# 1_MICROCONTROLADOR.net
KiCad netlist of a schematic drawn in Altium Designer
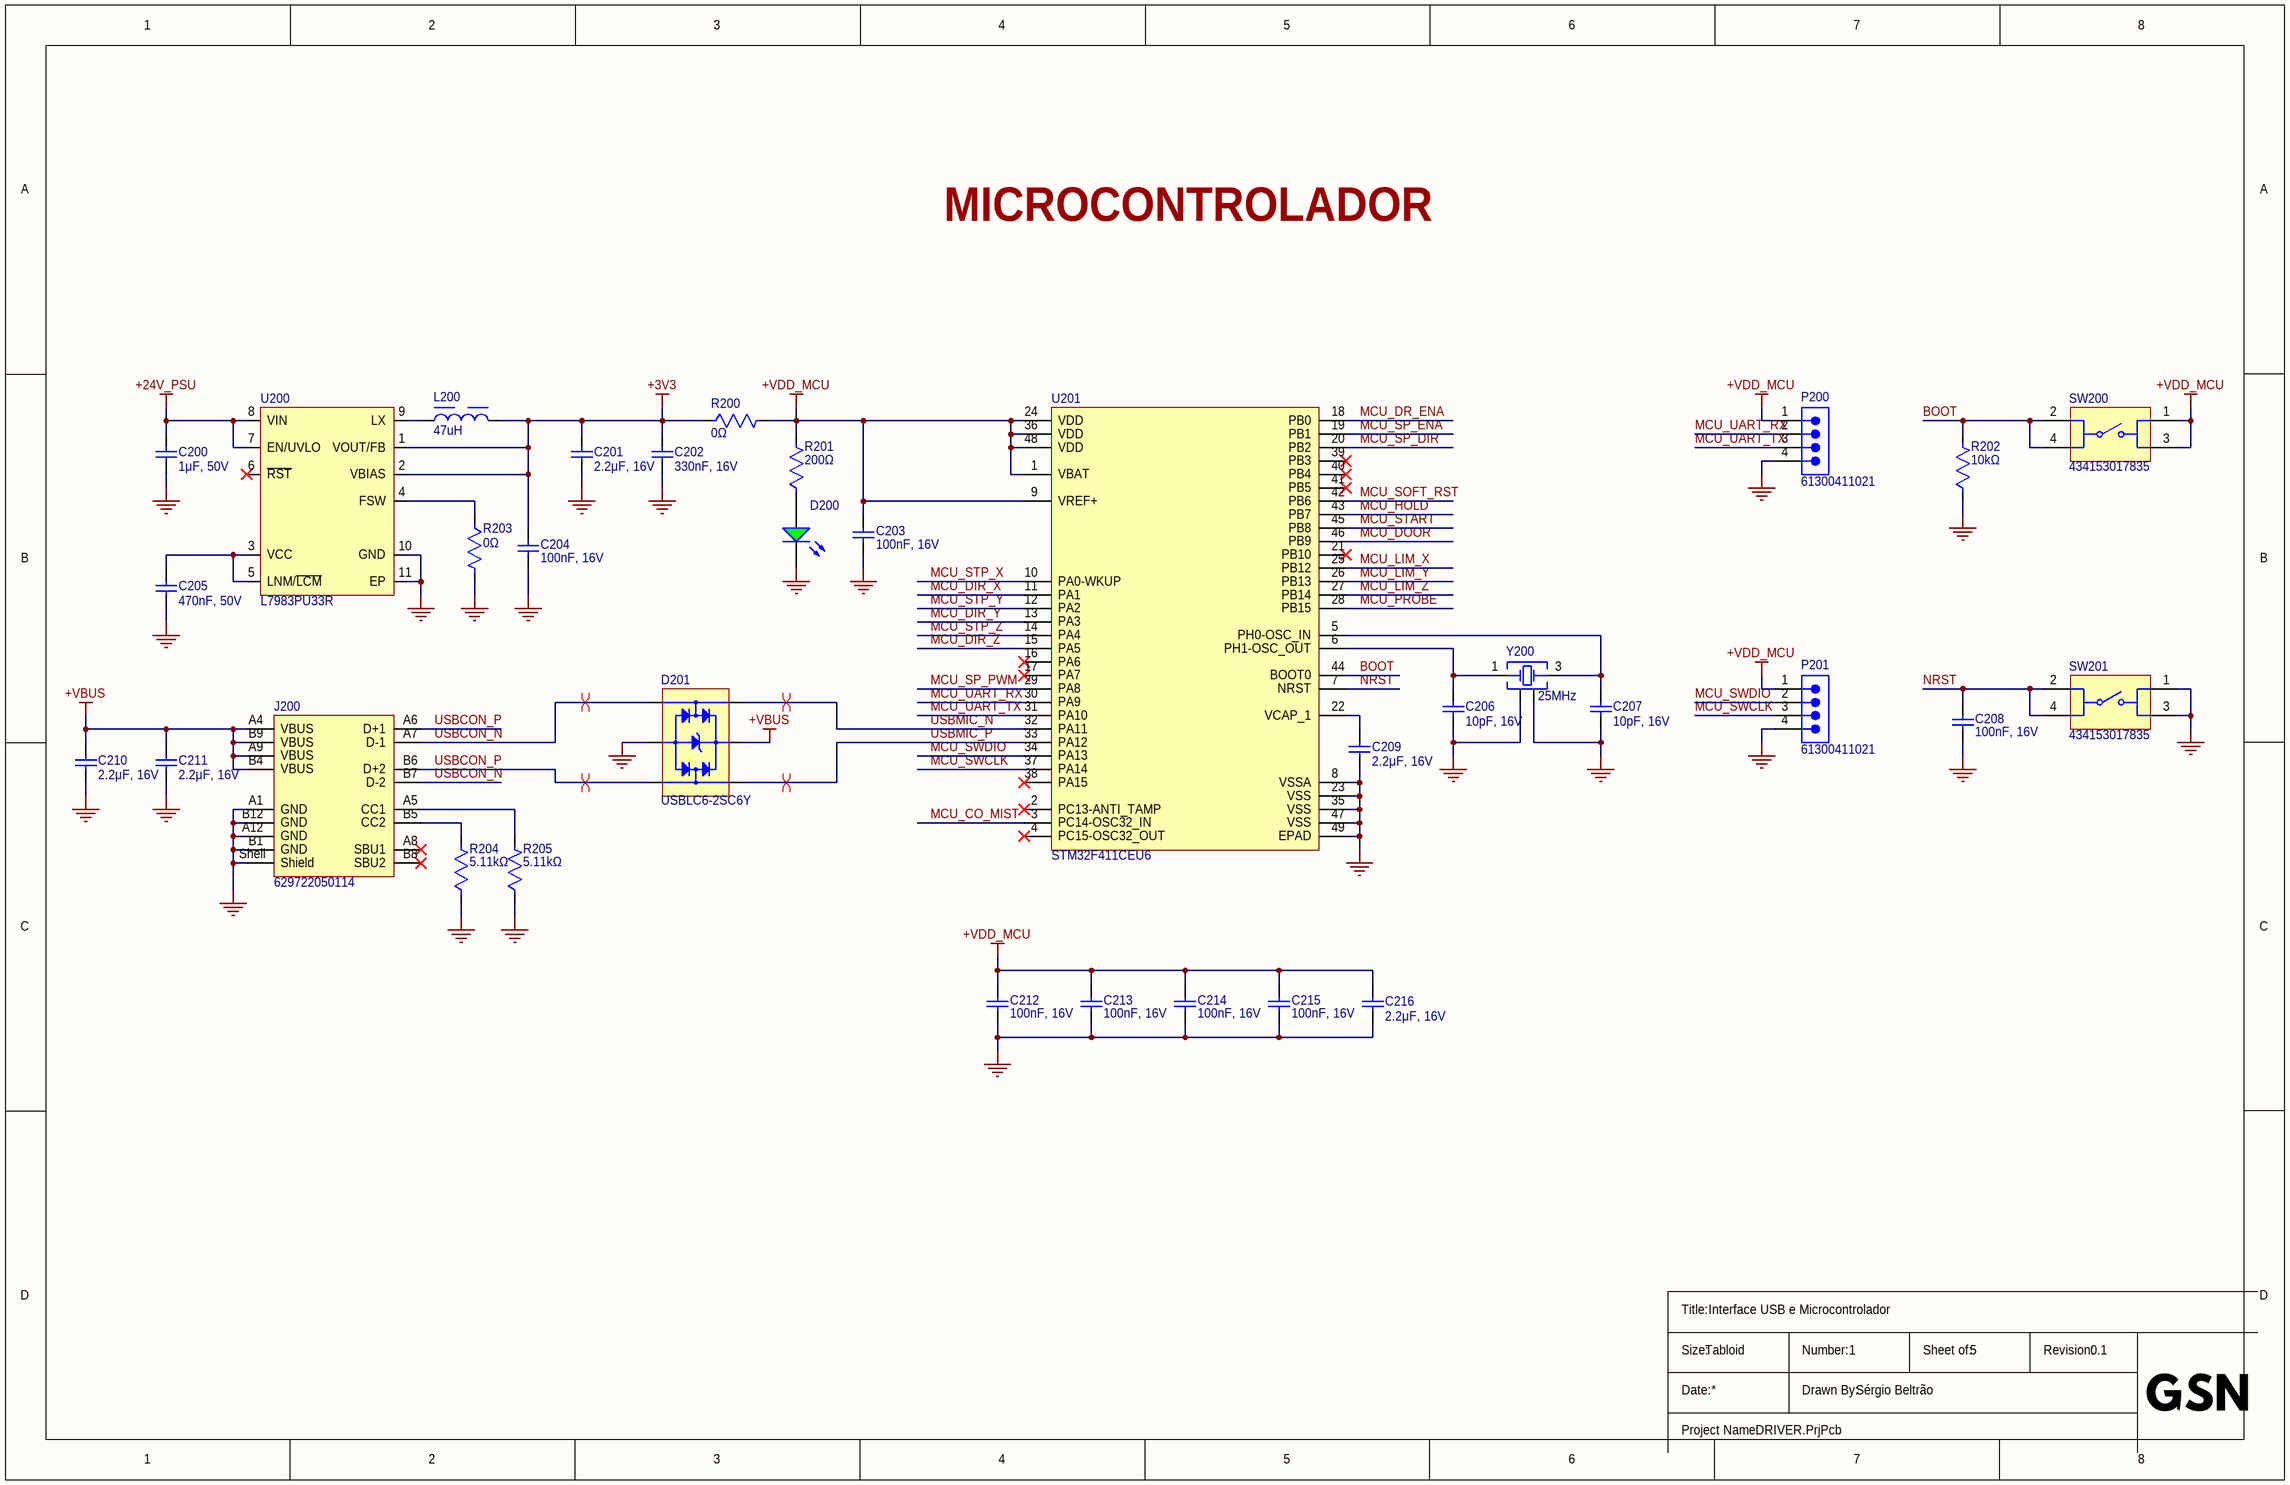
[diagram p0: 1_MICROCONTROLADOR.SchDoc]

(export (version "E")
  (design (tool "Eeschema 10.0.6"))
  (components
    (comp (ref "C200")
      (value "1μF, 50V")
      (footprint "WCAP-CSGP_0805_L2W1.25H1.25")
      (description "WCAP-CSGP Multilayer Ceramic Chip Capacitor, General Purpose, size 0805, 1μF, 50V")
      (fields
        (field (name "MANUFACTURER PART NUMBER") "885012207103R")
        (field (name "MANUFACTURER") "Wurth Elektronik")
      )
      (libsource (lib "WE - Passive Components") (part "Capacitor_Non-Polarized"))
    )
    (comp (ref "C201")
      (value "2.2μF, 16V")
      (footprint "WCAP-CSGP_0603_L1.6W0.8H0.8_Wave")
      (description "WCAP-CSGP Multilayer Ceramic Chip Capacitor, General Purpose, size 0603, 2.2μF, 16V")
      (fields
        (field (name "MANUFACTURER PART NUMBER") "885012106029")
        (field (name "MANUFACTURER") "Wurth Elektronik")
      )
      (libsource (lib "WE - Passive Components") (part "Capacitor_Non-Polarized"))
    )
    (comp (ref "C202")
      (value "330nF, 16V")
      (footprint "WCAP-CSGP_0603_L1.6W0.8H0.8_Wave")
      (description "WCAP-CSGP Multilayer Ceramic Chip Capacitor, General Purpose, size 0603, 330nF, 16V")
      (fields
        (field (name "MANUFACTURER PART NUMBER") "885012206049")
        (field (name "MANUFACTURER") "Wurth Elektronik")
      )
      (libsource (lib "WE - Passive Components") (part "Capacitor_Non-Polarized"))
    )
    (comp (ref "C203")
      (value "100nF, 16V")
      (footprint "WCAP-CSGP_0603_L1.6W0.8H0.8_Wave")
      (description "WCAP-CSGP Multilayer Ceramic Chip Capacitor, General Purpose, size 0603, 100nF, 16V")
      (fields
        (field (name "MANUFACTURER PART NUMBER") "885012206046")
        (field (name "MANUFACTURER") "Wurth Elektronik")
      )
      (libsource (lib "WE - Passive Components") (part "Capacitor_Non-Polarized"))
    )
    (comp (ref "C204")
      (value "100nF, 16V")
      (footprint "WCAP-CSGP_0603_L1.6W0.8H0.8_Wave")
      (description "WCAP-CSGP Multilayer Ceramic Chip Capacitor, General Purpose, size 0603, 100nF, 16V")
      (fields
        (field (name "MANUFACTURER PART NUMBER") "885012206046")
        (field (name "MANUFACTURER") "Wurth Elektronik")
      )
      (libsource (lib "WE - Passive Components") (part "Capacitor_Non-Polarized"))
    )
    (comp (ref "C205")
      (value "470nF, 50V")
      (footprint "WCAP-CSGP_0805_L2W1.25H1.25")
      (description "WCAP-CSGP Multilayer Ceramic Chip Capacitor, General Purpose, size 0805, 470nF, 50V")
      (fields
        (field (name "MANUFACTURER PART NUMBER") "885012207102")
        (field (name "MANUFACTURER") "Wurth Elektronik")
      )
      (libsource (lib "WE - Passive Components") (part "Capacitor_Non-Polarized"))
    )
    (comp (ref "C206")
      (value "10pF, 16V")
      (footprint "WCAP-CSGP_0603_L1.6W0.8H0.8_Wave")
      (description "WCAP-CSGP Multilayer Ceramic Chip Capacitor, General Purpose, size 0603, 10pF, 16V")
      (fields
        (field (name "MANUFACTURER PART NUMBER") "885012006017")
        (field (name "MANUFACTURER") "Wurth Elektronik")
      )
      (libsource (lib "WE - Passive Components") (part "Capacitor_Non-Polarized"))
    )
    (comp (ref "C207")
      (value "10pF, 16V")
      (footprint "WCAP-CSGP_0603_L1.6W0.8H0.8_Wave")
      (description "WCAP-CSGP Multilayer Ceramic Chip Capacitor, General Purpose, size 0603, 10pF, 16V")
      (fields
        (field (name "MANUFACTURER PART NUMBER") "885012006017")
        (field (name "MANUFACTURER") "Wurth Elektronik")
      )
      (libsource (lib "WE - Passive Components") (part "Capacitor_Non-Polarized"))
    )
    (comp (ref "C208")
      (value "100nF, 16V")
      (footprint "WCAP-CSGP_0603_L1.6W0.8H0.8_Wave")
      (description "WCAP-CSGP Multilayer Ceramic Chip Capacitor, General Purpose, size 0603, 100nF, 16V")
      (fields
        (field (name "MANUFACTURER PART NUMBER") "885012206046")
        (field (name "MANUFACTURER") "Wurth Elektronik")
      )
      (libsource (lib "WE - Passive Components") (part "Capacitor_Non-Polarized"))
    )
    (comp (ref "C209")
      (value "2.2μF, 16V")
      (footprint "WCAP-CSGP_0603_L1.6W0.8H0.8_Wave")
      (description "WCAP-CSGP Multilayer Ceramic Chip Capacitor, General Purpose, size 0603, 2.2μF, 16V")
      (fields
        (field (name "MANUFACTURER PART NUMBER") "885012106029")
        (field (name "MANUFACTURER") "Wurth Elektronik")
      )
      (libsource (lib "WE - Passive Components") (part "Capacitor_Non-Polarized"))
    )
    (comp (ref "C210")
      (value "2.2μF, 16V")
      (footprint "WCAP-CSGP_0603_L1.6W0.8H0.8_Wave")
      (description "WCAP-CSGP Multilayer Ceramic Chip Capacitor, General Purpose, size 0603, 2.2μF, 16V")
      (fields
        (field (name "MANUFACTURER PART NUMBER") "885012106029")
        (field (name "MANUFACTURER") "Wurth Elektronik")
      )
      (libsource (lib "WE - Passive Components") (part "Capacitor_Non-Polarized"))
    )
    (comp (ref "C211")
      (value "2.2μF, 16V")
      (footprint "WCAP-CSGP_0603_L1.6W0.8H0.8_Wave")
      (description "WCAP-CSGP Multilayer Ceramic Chip Capacitor, General Purpose, size 0603, 2.2μF, 16V")
      (fields
        (field (name "MANUFACTURER PART NUMBER") "885012106029")
        (field (name "MANUFACTURER") "Wurth Elektronik")
      )
      (libsource (lib "WE - Passive Components") (part "Capacitor_Non-Polarized"))
    )
    (comp (ref "C212")
      (value "100nF, 16V")
      (footprint "WCAP-CSGP_0603_L1.6W0.8H0.8_Wave")
      (description "WCAP-CSGP Multilayer Ceramic Chip Capacitor, General Purpose, size 0603, 100nF, 16V")
      (fields
        (field (name "MANUFACTURER PART NUMBER") "885012206046")
        (field (name "MANUFACTURER") "Wurth Elektronik")
      )
      (libsource (lib "WE - Passive Components") (part "Capacitor_Non-Polarized"))
    )
    (comp (ref "C213")
      (value "100nF, 16V")
      (footprint "WCAP-CSGP_0603_L1.6W0.8H0.8_Wave")
      (description "WCAP-CSGP Multilayer Ceramic Chip Capacitor, General Purpose, size 0603, 100nF, 16V")
      (fields
        (field (name "MANUFACTURER PART NUMBER") "885012206046")
        (field (name "MANUFACTURER") "Wurth Elektronik")
      )
      (libsource (lib "WE - Passive Components") (part "Capacitor_Non-Polarized"))
    )
    (comp (ref "C214")
      (value "100nF, 16V")
      (footprint "WCAP-CSGP_0603_L1.6W0.8H0.8_Wave")
      (description "WCAP-CSGP Multilayer Ceramic Chip Capacitor, General Purpose, size 0603, 100nF, 16V")
      (fields
        (field (name "MANUFACTURER PART NUMBER") "885012206046")
        (field (name "MANUFACTURER") "Wurth Elektronik")
      )
      (libsource (lib "WE - Passive Components") (part "Capacitor_Non-Polarized"))
    )
    (comp (ref "C215")
      (value "100nF, 16V")
      (footprint "WCAP-CSGP_0603_L1.6W0.8H0.8_Wave")
      (description "WCAP-CSGP Multilayer Ceramic Chip Capacitor, General Purpose, size 0603, 100nF, 16V")
      (fields
        (field (name "MANUFACTURER PART NUMBER") "885012206046")
        (field (name "MANUFACTURER") "Wurth Elektronik")
      )
      (libsource (lib "WE - Passive Components") (part "Capacitor_Non-Polarized"))
    )
    (comp (ref "C216")
      (value "2.2μF, 16V")
      (footprint "WCAP-CSGP_0603_L1.6W0.8H0.8_Wave")
      (description "WCAP-CSGP Multilayer Ceramic Chip Capacitor, General Purpose, size 0603, 2.2μF, 16V")
      (fields
        (field (name "MANUFACTURER PART NUMBER") "885012106029")
        (field (name "MANUFACTURER") "Wurth Elektronik")
      )
      (libsource (lib "WE - Passive Components") (part "Capacitor_Non-Polarized"))
    )
    (comp (ref "D200")
      (value "Bright Green, 2V, 140deg")
      (footprint "WL-SMCW_0603_150060xx75000")
      (description "WL-SMCW Mono-color Chip LED Waterclear, SMT, size 0603, Bright Green, 2V, 140°")
      (fields
        (field (name "MANUFACTURER PART NUMBER") "150060VS75000")
        (field (name "MANUFACTURER") "Wurth Elektronik")
      )
      (libsource (lib "WE - Optoelectronic Components") (part "LED_Green_2A-1K"))
    )
    (comp (ref "D201")
      (value "USBLC6-2SC6Y")
      (footprint "SOT-23-6")
      (description "TVS DIODE 5.25VWM 17VC SOT23-6")
      (fields (field (name "MANUFACTURER") "STMicroelectronics"))
      (libsource (lib "TVS-Diodes") (part "USBLC6-2SC6Y"))
    )
    (comp (ref "J200")
      (value "629722050114")
      (footprint "629722050114")
      (description "WR-COM USB 2.0 Vertical SMT")
      (fields (field (name "MANUFACTURER") "Wurth Elektronik"))
      (libsource (lib "WE - Electromechanical Components") (part "USB 2.0_Type C_Receptacle_1 Port"))
    )
    (comp (ref "L200")
      (value "47uH")
      (footprint "WE-MAIA_3015")
      (description "WE-MAIA SMT Power Inductor, size 3015, 47uH, 0.5A, 2300mohm")
      (fields
        (field (name "MANUFACTURER PART NUMBER") "78438335470")
        (field (name "MANUFACTURER") "Wurth Elektronik")
      )
      (libsource (lib "WE - Passive Components") (part "Inductor - 3"))
    )
    (comp (ref "P200")
      (value "61300411021")
      (footprint "61300411021")
      (description "WR-PHD Pin Header, THT, Angled, pitch 2.54mm, 1 Row, 4P")
      (fields (field (name "MANUFACTURER") "Wurth Elektronik"))
      (libsource (lib "WE - Electromechanical Components") (part "Header_Male_1R_04P"))
    )
    (comp (ref "P201")
      (value "61300411021")
      (footprint "61300411021")
      (description "WR-PHD Pin Header, THT, Angled, pitch 2.54mm, 1 Row, 4P")
      (fields (field (name "MANUFACTURER") "Wurth Elektronik"))
      (libsource (lib "WE - Electromechanical Components") (part "Header_Male_1R_04P"))
    )
    (comp (ref "R200")
      (value "0Ω")
      (footprint "0805-WAVE")
      (description "RES 0 OHM 1% 1/8W 0805")
      (fields
        (field (name "MANUFACTURER") "Yageo Group")
        (field (name "MANUFACTURER PART NUMBER") "RC0805FR-070RL")
      )
      (libsource (lib "Resistors-0805-E96-Yageo") (part "RC0805FR-070RL"))
    )
    (comp (ref "R201")
      (value "200Ω")
      (footprint "0603-WAVE")
      (description "RES 200 OHM 1% 1/10W 0603")
      (fields
        (field (name "MANUFACTURER PART NUMBER") "RC0603FR-07200RL")
        (field (name "MANUFACTURER") "Yageo Group")
      )
      (libsource (lib "Resistors-0603-E96-Yageo") (part "RC0603FR-07200RL"))
    )
    (comp (ref "R202")
      (value "10kΩ")
      (footprint "0603-WAVE")
      (description "RES 10K OHM 1% 1/10W 0603")
      (fields
        (field (name "MANUFACTURER PART NUMBER") "RC0603FR-0710KL")
        (field (name "MANUFACTURER") "Yageo Group")
      )
      (libsource (lib "Resistors-0603-E96-Yageo") (part "RC0603FR-0710KL"))
    )
    (comp (ref "R203")
      (value "0Ω")
      (footprint "0603-WAVE")
      (description "RES 0 OHM 1% 1/10W 0603")
      (fields
        (field (name "MANUFACTURER PART NUMBER") "RC0603FR-070RL")
        (field (name "MANUFACTURER") "Yageo Group")
      )
      (libsource (lib "Resistors-0603-E96-Yageo") (part "RC0603FR-070RL"))
    )
    (comp (ref "R204")
      (value "5.11kΩ")
      (footprint "0603-WAVE")
      (description "RES 5.11K OHM 1% 1/10W 0603")
      (fields
        (field (name "MANUFACTURER PART NUMBER") "RC0603FR-075K11L")
        (field (name "MANUFACTURER") "Yageo Group")
      )
      (libsource (lib "Resistors-0603-E96-Yageo") (part "RC0603FR-075K11L"))
    )
    (comp (ref "R205")
      (value "5.11kΩ")
      (footprint "0603-WAVE")
      (description "RES 5.11K OHM 1% 1/10W 0603")
      (fields
        (field (name "MANUFACTURER PART NUMBER") "RC0603FR-075K11L")
        (field (name "MANUFACTURER") "Yageo Group")
      )
      (libsource (lib "Resistors-0603-E96-Yageo") (part "RC0603FR-075K11L"))
    )
    (comp (ref "SW200")
      (value "434153017835")
      (footprint "434153017835")
      (description "WS-TASV J-Bend SMT Tact Switch, 3.5mm x 2.9mm x 1.7mm, SPST-NO, 350gf, 12V, 50mA")
      (fields (field (name "MANUFACTURER") "Wurth Elektronik"))
      (libsource (lib "WE - Electromechanical Components") (part "SPST-NO_4P_24-13"))
    )
    (comp (ref "SW201")
      (value "434153017835")
      (footprint "434153017835")
      (description "WS-TASV J-Bend SMT Tact Switch, 3.5mm x 2.9mm x 1.7mm, SPST-NO, 350gf, 12V, 50mA")
      (fields (field (name "MANUFACTURER") "Wurth Elektronik"))
      (libsource (lib "WE - Electromechanical Components") (part "SPST-NO_4P_24-13"))
    )
    (comp (ref "U200")
      (value "L7983PU33R")
      (footprint "10-WFDFN-EP")
      (description "IC REG BUCK 3.3V 300MA 10DFN")
      (fields (field (name "MANUFACTURER") "STMicroelectronics"))
      (libsource (lib "Voltage-Regulators") (part "L7983PU33R"))
    )
    (comp (ref "U201")
      (value "STM32F411CEU6")
      (footprint "UFQFN-48-7X7_EXPOSED_PAD")
      (description "IC MCU 32BIT 512KB FLSH 48UFQFPN")
      (fields (field (name "MANUFACTURER") "STMicroelectronics"))
      (libsource (lib "Microcontrollers") (part "STM32F411CEU6"))
    )
    (comp (ref "Y200")
      (value "25MHz")
      (footprint "WE-XTAL_IQXC-42")
      (description "WE-XTAL Quartz Crystal, IQXC-42, 25MHz, +/-15ppm")
      (fields
        (field (name "MANUFACTURER PART NUMBER") "830069494")
        (field (name "MANUFACTURER") "Wurth Elektronik")
      )
      (libsource (lib "WE - Passive Components") (part "WE-XTAL_IQXC-42"))
    )
  )
  (nets
    (net (code "1") (name "+3V3") (class "Default")
      (node (ref "C201") (pin "2") (pinfunction "2_2") (pintype "passive"))
      (node (ref "C202") (pin "2") (pinfunction "2_2") (pintype "passive"))
      (node (ref "C204") (pin "2") (pinfunction "2_2") (pintype "passive"))
      (node (ref "L200") (pin "2") (pinfunction "2_2") (pintype "passive"))
      (node (ref "R200") (pin "1") (pinfunction "1_1") (pintype "passive"))
      (node (ref "U200") (pin "1") (pinfunction "VOUT/FB_1") (pintype "passive"))
      (node (ref "U200") (pin "2") (pinfunction "VBIAS_2") (pintype "passive"))
    )
    (net (code "2") (name "+24V_PSU") (class "Default")
      (node (ref "C200") (pin "2") (pinfunction "2_2") (pintype "passive"))
      (node (ref "U200") (pin "7") (pinfunction "EN/UVLO_7") (pintype "passive"))
      (node (ref "U200") (pin "8") (pinfunction "VIN_8") (pintype "passive"))
    )
    (net (code "3") (name "+VBUS") (class "Default")
      (node (ref "C210") (pin "2") (pinfunction "2_2") (pintype "passive"))
      (node (ref "C211") (pin "2") (pinfunction "2_2") (pintype "passive"))
      (node (ref "D201") (pin "5") (pinfunction "VBUS_5") (pintype "passive"))
      (node (ref "J200") (pin "A4") (pinfunction "VBUS_A4") (pintype "passive"))
      (node (ref "J200") (pin "A9") (pinfunction "VBUS_A9") (pintype "passive"))
      (node (ref "J200") (pin "B4") (pinfunction "VBUS_B4") (pintype "passive"))
      (node (ref "J200") (pin "B9") (pinfunction "VBUS_B9") (pintype "passive"))
    )
    (net (code "4") (name "+VDD_MCU") (class "Default")
      (node (ref "C203") (pin "2") (pinfunction "2_2") (pintype "passive"))
      (node (ref "C212") (pin "2") (pinfunction "2_2") (pintype "passive"))
      (node (ref "C213") (pin "2") (pinfunction "2_2") (pintype "passive"))
      (node (ref "C214") (pin "2") (pinfunction "2_2") (pintype "passive"))
      (node (ref "C215") (pin "2") (pinfunction "2_2") (pintype "passive"))
      (node (ref "C216") (pin "2") (pinfunction "2_2") (pintype "passive"))
      (node (ref "P200") (pin "1") (pinfunction "1_1") (pintype "passive"))
      (node (ref "P201") (pin "1") (pinfunction "1_1") (pintype "passive"))
      (node (ref "R200") (pin "2") (pinfunction "2_2") (pintype "passive"))
      (node (ref "R201") (pin "2") (pinfunction "2_2") (pintype "passive"))
      (node (ref "SW200") (pin "1") (pinfunction "1_1") (pintype "passive"))
      (node (ref "SW200") (pin "3") (pinfunction "3_3") (pintype "passive"))
      (node (ref "U201") (pin "1") (pinfunction "VBAT_1") (pintype "passive"))
      (node (ref "U201") (pin "24") (pinfunction "VDD_24") (pintype "passive"))
      (node (ref "U201") (pin "36") (pinfunction "VDD_36") (pintype "passive"))
      (node (ref "U201") (pin "48") (pinfunction "VDD_48") (pintype "passive"))
      (node (ref "U201") (pin "9") (pinfunction "VREF+_9") (pintype "passive"))
    )
    (net (code "5") (name "/BOOT") (class "Default")
      (node (ref "R202") (pin "2") (pinfunction "2_2") (pintype "passive"))
      (node (ref "SW200") (pin "2") (pinfunction "2_2") (pintype "passive"))
      (node (ref "SW200") (pin "4") (pinfunction "4_4") (pintype "passive"))
      (node (ref "U201") (pin "44") (pinfunction "BOOT0_44") (pintype "passive"))
    )
    (net (code "6") (name "/MCU_CO_MIST") (class "Default")
      (node (ref "U201") (pin "3") (pinfunction "PC14-OSC32_IN_3") (pintype "passive"))
    )
    (net (code "7") (name "/MCU_DIR_X") (class "Default")
      (node (ref "U201") (pin "11") (pinfunction "PA1_11") (pintype "passive"))
    )
    (net (code "8") (name "/MCU_DIR_Y") (class "Default")
      (node (ref "U201") (pin "13") (pinfunction "PA3_13") (pintype "passive"))
    )
    (net (code "9") (name "/MCU_DIR_Z") (class "Default")
      (node (ref "U201") (pin "15") (pinfunction "PA5_15") (pintype "passive"))
    )
    (net (code "10") (name "/MCU_DOOR") (class "Default")
      (node (ref "U201") (pin "46") (pinfunction "PB9_46") (pintype "passive"))
    )
    (net (code "11") (name "/MCU_DR_ENA") (class "Default")
      (node (ref "U201") (pin "18") (pinfunction "PB0_18") (pintype "passive"))
    )
    (net (code "12") (name "/MCU_HOLD") (class "Default")
      (node (ref "U201") (pin "43") (pinfunction "PB7_43") (pintype "passive"))
    )
    (net (code "13") (name "/MCU_LIM_X") (class "Default")
      (node (ref "U201") (pin "25") (pinfunction "PB12_25") (pintype "passive"))
    )
    (net (code "14") (name "/MCU_LIM_Y") (class "Default")
      (node (ref "U201") (pin "26") (pinfunction "PB13_26") (pintype "passive"))
    )
    (net (code "15") (name "/MCU_LIM_Z") (class "Default")
      (node (ref "U201") (pin "27") (pinfunction "PB14_27") (pintype "passive"))
    )
    (net (code "16") (name "/MCU_PROBE") (class "Default")
      (node (ref "U201") (pin "28") (pinfunction "PB15_28") (pintype "passive"))
    )
    (net (code "17") (name "/MCU_SOFT_RST") (class "Default")
      (node (ref "U201") (pin "42") (pinfunction "PB6_42") (pintype "passive"))
    )
    (net (code "18") (name "/MCU_SP_DIR") (class "Default")
      (node (ref "U201") (pin "20") (pinfunction "PB2_20") (pintype "passive"))
    )
    (net (code "19") (name "/MCU_SP_ENA") (class "Default")
      (node (ref "U201") (pin "19") (pinfunction "PB1_19") (pintype "passive"))
    )
    (net (code "20") (name "/MCU_SP_PWM") (class "Default")
      (node (ref "U201") (pin "29") (pinfunction "PA8_29") (pintype "passive"))
    )
    (net (code "21") (name "/MCU_START") (class "Default")
      (node (ref "U201") (pin "45") (pinfunction "PB8_45") (pintype "passive"))
    )
    (net (code "22") (name "/MCU_STP_X") (class "Default")
      (node (ref "U201") (pin "10") (pinfunction "PA0-WKUP_10") (pintype "passive"))
    )
    (net (code "23") (name "/MCU_STP_Y") (class "Default")
      (node (ref "U201") (pin "12") (pinfunction "PA2_12") (pintype "passive"))
    )
    (net (code "24") (name "/MCU_STP_Z") (class "Default")
      (node (ref "U201") (pin "14") (pinfunction "PA4_14") (pintype "passive"))
    )
    (net (code "25") (name "/MCU_SWCLK") (class "Default")
      (node (ref "P201") (pin "3") (pinfunction "3_3") (pintype "passive"))
      (node (ref "U201") (pin "37") (pinfunction "PA14_37") (pintype "passive"))
    )
    (net (code "26") (name "/MCU_SWDIO") (class "Default")
      (node (ref "P201") (pin "2") (pinfunction "2_2") (pintype "passive"))
      (node (ref "U201") (pin "34") (pinfunction "PA13_34") (pintype "passive"))
    )
    (net (code "27") (name "/MCU_UART_RX") (class "Default")
      (node (ref "P200") (pin "2") (pinfunction "2_2") (pintype "passive"))
      (node (ref "U201") (pin "30") (pinfunction "PA9_30") (pintype "passive"))
    )
    (net (code "28") (name "/MCU_UART_TX") (class "Default")
      (node (ref "P200") (pin "3") (pinfunction "3_3") (pintype "passive"))
      (node (ref "U201") (pin "31") (pinfunction "PA10_31") (pintype "passive"))
    )
    (net (code "29") (name "/NRST") (class "Default")
      (node (ref "C208") (pin "2") (pinfunction "2_2") (pintype "passive"))
      (node (ref "SW201") (pin "2") (pinfunction "2_2") (pintype "passive"))
      (node (ref "SW201") (pin "4") (pinfunction "4_4") (pintype "passive"))
      (node (ref "U201") (pin "7") (pinfunction "NRST_7") (pintype "passive"))
    )
    (net (code "30") (name "/USBCON_N") (class "Default")
      (node (ref "D201") (pin "1") (pinfunction "IO1_1") (pintype "passive"))
      (node (ref "J200") (pin "A7") (pinfunction "D-1_A7") (pintype "passive"))
      (node (ref "J200") (pin "B7") (pinfunction "D-2_B7") (pintype "passive"))
    )
    (net (code "31") (name "/USBCON_P") (class "Default")
      (node (ref "D201") (pin "3") (pinfunction "IO2_3") (pintype "passive"))
      (node (ref "J200") (pin "A6") (pinfunction "D+1_A6") (pintype "passive"))
      (node (ref "J200") (pin "B6") (pinfunction "D+2_B6") (pintype "passive"))
    )
    (net (code "32") (name "/USBMIC_N") (class "Default")
      (node (ref "D201") (pin "6") (pinfunction "IO1_6") (pintype "passive"))
      (node (ref "U201") (pin "32") (pinfunction "PA11_32") (pintype "passive"))
    )
    (net (code "33") (name "/USBMIC_P") (class "Default")
      (node (ref "D201") (pin "4") (pinfunction "IO2_4") (pintype "passive"))
      (node (ref "U201") (pin "33") (pinfunction "PA12_33") (pintype "passive"))
    )
    (net (code "34") (name "GND") (class "Default")
      (node (ref "C200") (pin "1") (pinfunction "1_1") (pintype "passive"))
      (node (ref "C201") (pin "1") (pinfunction "1_1") (pintype "passive"))
      (node (ref "C202") (pin "1") (pinfunction "1_1") (pintype "passive"))
      (node (ref "C203") (pin "1") (pinfunction "1_1") (pintype "passive"))
      (node (ref "C204") (pin "1") (pinfunction "1_1") (pintype "passive"))
      (node (ref "C205") (pin "1") (pinfunction "1_1") (pintype "passive"))
      (node (ref "C206") (pin "1") (pinfunction "1_1") (pintype "passive"))
      (node (ref "C207") (pin "1") (pinfunction "1_1") (pintype "passive"))
      (node (ref "C208") (pin "1") (pinfunction "1_1") (pintype "passive"))
      (node (ref "C209") (pin "1") (pinfunction "1_1") (pintype "passive"))
      (node (ref "C210") (pin "1") (pinfunction "1_1") (pintype "passive"))
      (node (ref "C211") (pin "1") (pinfunction "1_1") (pintype "passive"))
      (node (ref "C212") (pin "1") (pinfunction "1_1") (pintype "passive"))
      (node (ref "C213") (pin "1") (pinfunction "1_1") (pintype "passive"))
      (node (ref "C214") (pin "1") (pinfunction "1_1") (pintype "passive"))
      (node (ref "C215") (pin "1") (pinfunction "1_1") (pintype "passive"))
      (node (ref "C216") (pin "1") (pinfunction "1_1") (pintype "passive"))
      (node (ref "D200") (pin "1") (pinfunction "K_1") (pintype "passive"))
      (node (ref "D201") (pin "2") (pinfunction "GND_2") (pintype "passive"))
      (node (ref "J200") (pin "A1") (pinfunction "GND_A1") (pintype "passive"))
      (node (ref "J200") (pin "A12") (pinfunction "GND_A12") (pintype "passive"))
      (node (ref "J200") (pin "B1") (pinfunction "GND_B1") (pintype "passive"))
      (node (ref "J200") (pin "B12") (pinfunction "GND_B12") (pintype "passive"))
      (node (ref "J200") (pin "Shell") (pinfunction "Shield_Shell") (pintype "passive"))
      (node (ref "P200") (pin "4") (pinfunction "4_4") (pintype "passive"))
      (node (ref "P201") (pin "4") (pinfunction "4_4") (pintype "passive"))
      (node (ref "R202") (pin "1") (pinfunction "1_1") (pintype "passive"))
      (node (ref "R203") (pin "2") (pinfunction "2_2") (pintype "passive"))
      (node (ref "R204") (pin "1") (pinfunction "1_1") (pintype "passive"))
      (node (ref "R205") (pin "1") (pinfunction "1_1") (pintype "passive"))
      (node (ref "SW201") (pin "1") (pinfunction "1_1") (pintype "passive"))
      (node (ref "SW201") (pin "3") (pinfunction "3_3") (pintype "passive"))
      (node (ref "U200") (pin "10") (pinfunction "GND_10") (pintype "passive"))
      (node (ref "U200") (pin "11") (pinfunction "EP_11") (pintype "passive"))
      (node (ref "U201") (pin "23") (pinfunction "VSS_23") (pintype "passive"))
      (node (ref "U201") (pin "35") (pinfunction "VSS_35") (pintype "passive"))
      (node (ref "U201") (pin "47") (pinfunction "VSS_47") (pintype "passive"))
      (node (ref "U201") (pin "49") (pinfunction "EPAD_49") (pintype "passive"))
      (node (ref "U201") (pin "8") (pinfunction "VSSA_8") (pintype "passive"))
      (node (ref "Y200") (pin "2") (pinfunction "GND_&_Lid_2") (pintype "passive"))
      (node (ref "Y200") (pin "4") (pinfunction "GND_&_Lid_4") (pintype "passive"))
    )
    (net (code "35") (name "Net-(D200-A)") (class "Default")
      (node (ref "D200") (pin "2") (pinfunction "A_2") (pintype "passive"))
      (node (ref "R201") (pin "1") (pinfunction "1_1") (pintype "passive"))
    )
    (net (code "36") (name "Net-(J200-CC1)") (class "Default")
      (node (ref "J200") (pin "A5") (pinfunction "CC1_A5") (pintype "passive"))
      (node (ref "R205") (pin "2") (pinfunction "2_2") (pintype "passive"))
    )
    (net (code "37") (name "Net-(J200-CC2)") (class "Default")
      (node (ref "J200") (pin "B5") (pinfunction "CC2_B5") (pintype "passive"))
      (node (ref "R204") (pin "2") (pinfunction "2_2") (pintype "passive"))
    )
    (net (code "38") (name "Net-(U200-FSW)") (class "Default")
      (node (ref "R203") (pin "1") (pinfunction "1_1") (pintype "passive"))
      (node (ref "U200") (pin "4") (pinfunction "FSW_4") (pintype "passive"))
    )
    (net (code "39") (name "Net-(U200-LNM{slash}~{LCM})") (class "Default")
      (node (ref "C205") (pin "2") (pinfunction "2_2") (pintype "passive"))
      (node (ref "U200") (pin "3") (pinfunction "VCC_3") (pintype "passive"))
      (node (ref "U200") (pin "5") (pinfunction "LNM/~{LCM}_5") (pintype "passive"))
    )
    (net (code "40") (name "Net-(U200-LX)") (class "Default")
      (node (ref "L200") (pin "1") (pinfunction "1_1") (pintype "passive"))
      (node (ref "U200") (pin "9") (pinfunction "LX_9") (pintype "passive"))
    )
    (net (code "41") (name "Net-(U201-PH0-OSC_IN)") (class "Default")
      (node (ref "C207") (pin "2") (pinfunction "2_2") (pintype "passive"))
      (node (ref "U201") (pin "5") (pinfunction "PH0-OSC_IN_5") (pintype "passive"))
      (node (ref "Y200") (pin "3") (pinfunction "Crystal_3") (pintype "passive"))
    )
    (net (code "42") (name "Net-(U201-PH1-OSC_OUT)") (class "Default")
      (node (ref "C206") (pin "2") (pinfunction "2_2") (pintype "passive"))
      (node (ref "U201") (pin "6") (pinfunction "PH1-OSC_OUT_6") (pintype "passive"))
      (node (ref "Y200") (pin "1") (pinfunction "Crystal_1") (pintype "passive"))
    )
    (net (code "43") (name "Net-(U201-VCAP_1)") (class "Default")
      (node (ref "C209") (pin "2") (pinfunction "2_2") (pintype "passive"))
      (node (ref "U201") (pin "22") (pinfunction "VCAP_1_22") (pintype "passive"))
    )
    (net (code "44") (name "unconnected-(J200-SBU1-PadA8)") (class "Default")
      (node (ref "J200") (pin "A8") (pinfunction "SBU1_A8") (pintype "passive+no_connect"))
    )
    (net (code "45") (name "unconnected-(J200-SBU2-PadB8)") (class "Default")
      (node (ref "J200") (pin "B8") (pinfunction "SBU2_B8") (pintype "passive+no_connect"))
    )
    (net (code "46") (name "unconnected-(U200-~{RST}-Pad6)") (class "Default")
      (node (ref "U200") (pin "6") (pinfunction "~{RST}_6") (pintype "passive+no_connect"))
    )
    (net (code "47") (name "unconnected-(U201-PA6-Pad16)") (class "Default")
      (node (ref "U201") (pin "16") (pinfunction "PA6_16") (pintype "passive+no_connect"))
    )
    (net (code "48") (name "unconnected-(U201-PA7-Pad17)") (class "Default")
      (node (ref "U201") (pin "17") (pinfunction "PA7_17") (pintype "passive+no_connect"))
    )
    (net (code "49") (name "unconnected-(U201-PA15-Pad38)") (class "Default")
      (node (ref "U201") (pin "38") (pinfunction "PA15_38") (pintype "passive+no_connect"))
    )
    (net (code "50") (name "unconnected-(U201-PB3-Pad39)") (class "Default")
      (node (ref "U201") (pin "39") (pinfunction "PB3_39") (pintype "passive+no_connect"))
    )
    (net (code "51") (name "unconnected-(U201-PB4-Pad40)") (class "Default")
      (node (ref "U201") (pin "40") (pinfunction "PB4_40") (pintype "passive+no_connect"))
    )
    (net (code "52") (name "unconnected-(U201-PB5-Pad41)") (class "Default")
      (node (ref "U201") (pin "41") (pinfunction "PB5_41") (pintype "passive+no_connect"))
    )
    (net (code "53") (name "unconnected-(U201-PB10-Pad21)") (class "Default")
      (node (ref "U201") (pin "21") (pinfunction "PB10_21") (pintype "passive+no_connect"))
    )
    (net (code "54") (name "unconnected-(U201-PC13-ANTI_TAMP-Pad2)") (class "Default")
      (node (ref "U201") (pin "2") (pinfunction "PC13-ANTI_TAMP_2") (pintype "passive+no_connect"))
    )
    (net (code "55") (name "unconnected-(U201-PC15-OSC32_OUT-Pad4)") (class "Default")
      (node (ref "U201") (pin "4") (pinfunction "PC15-OSC32_OUT_4") (pintype "passive+no_connect"))
    )
  )
)
